# DINOBUS.net
KiCad netlist of a schematic drawn in Altium Designer
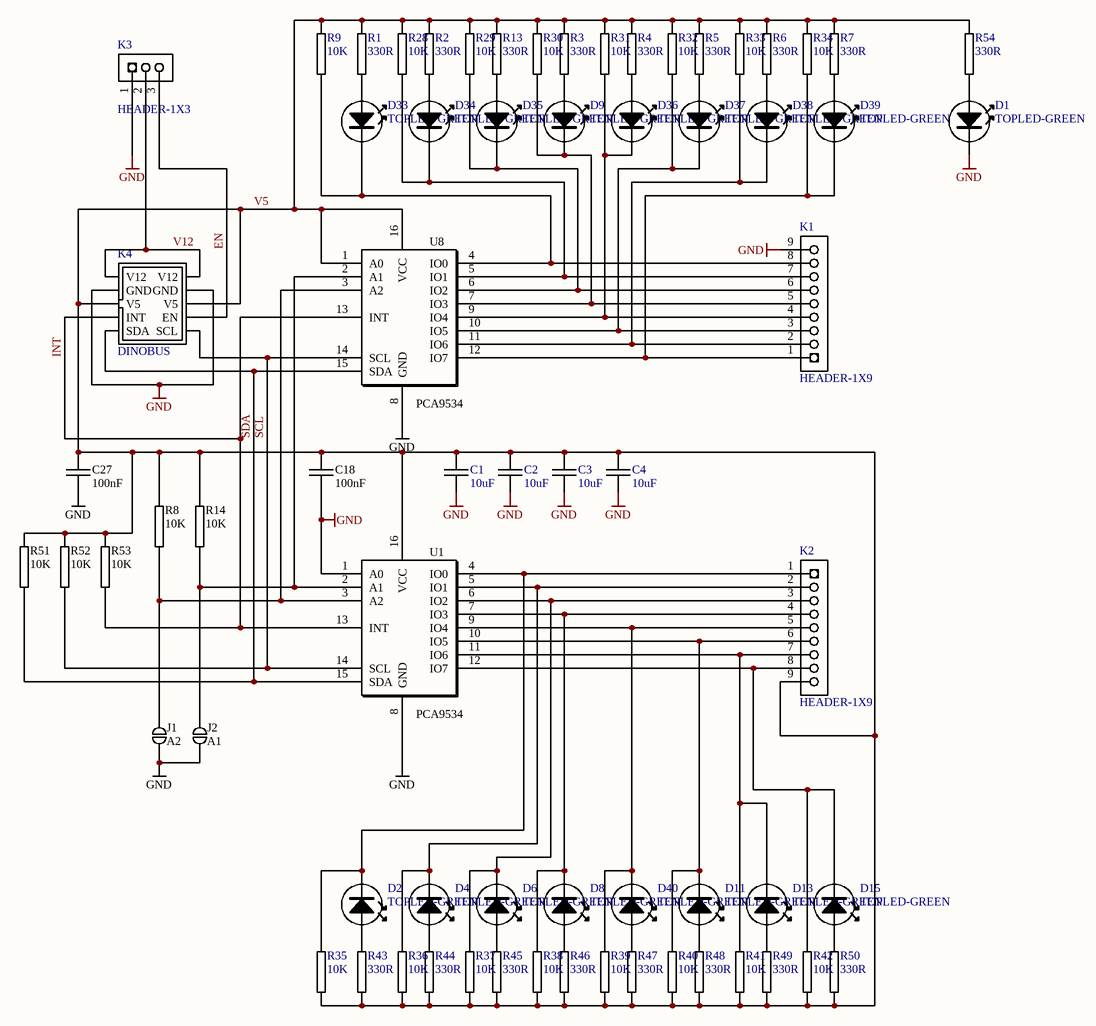
[diagram p0: DINOBUS .SchDoc]

(export (version "E")
  (design (tool "Eeschema 10.0.6"))
  (components
    (comp (ref "C1")
      (value "10uF")
      (footprint "0805C-GENERIC")
      (description "CAPACITOR 0805 CERAMIC")
      (fields
        (field (name "MANUFACTURER PART NUMBER") "C2012X5R1C106M")
        (field (name "MANUFACTURER") "TDK Corporation")
      )
      (libsource (lib "vh_Altium Library") (part "0805C-10UF-16V-X5R-TDK"))
    )
    (comp (ref "C2")
      (value "10uF")
      (footprint "0805C-GENERIC")
      (description "CAPACITOR 0805 CERAMIC")
      (fields
        (field (name "MANUFACTURER PART NUMBER") "C2012X5R1C106M")
        (field (name "MANUFACTURER") "TDK Corporation")
      )
      (libsource (lib "vh_Altium Library") (part "0805C-10UF-16V-X5R-TDK"))
    )
    (comp (ref "C3")
      (value "10uF")
      (footprint "0805C-GENERIC")
      (description "CAPACITOR 0805 CERAMIC")
      (fields
        (field (name "MANUFACTURER PART NUMBER") "C2012X5R1C106M")
        (field (name "MANUFACTURER") "TDK Corporation")
      )
      (libsource (lib "vh_Altium Library") (part "0805C-10UF-16V-X5R-TDK"))
    )
    (comp (ref "C4")
      (value "10uF")
      (footprint "0805C-GENERIC")
      (description "CAPACITOR 0805 CERAMIC")
      (fields
        (field (name "MANUFACTURER PART NUMBER") "C2012X5R1C106M")
        (field (name "MANUFACTURER") "TDK Corporation")
      )
      (libsource (lib "vh_Altium Library") (part "0805C-10UF-16V-X5R-TDK"))
    )
    (comp (ref "C18")
      (value "100nF")
      (footprint "0805C")
      (description "CAPACITOR NONPOLARISED")
      (libsource (lib "I2Csticks") (part "0805C-100NF"))
    )
    (comp (ref "C27")
      (value "100nF")
      (footprint "0805C")
      (description "CAPACITOR NONPOLARISED")
      (libsource (lib "I2Csticks") (part "0805C-100NF"))
    )
    (comp (ref "D1")
      (value "TOPLED-GREEN")
      (footprint "TOPLED-GREEN")
      (libsource (lib "vh_Altium Library") (part "TOPLED-GREEN"))
    )
    (comp (ref "D2")
      (value "TOPLED-GREEN")
      (footprint "TOPLED-GREEN")
      (libsource (lib "vh_Altium Library") (part "TOPLED-GREEN"))
    )
    (comp (ref "D4")
      (value "TOPLED-GREEN")
      (footprint "TOPLED-GREEN")
      (libsource (lib "vh_Altium Library") (part "TOPLED-GREEN"))
    )
    (comp (ref "D6")
      (value "TOPLED-GREEN")
      (footprint "TOPLED-GREEN")
      (libsource (lib "vh_Altium Library") (part "TOPLED-GREEN"))
    )
    (comp (ref "D8")
      (value "TOPLED-GREEN")
      (footprint "TOPLED-GREEN")
      (libsource (lib "vh_Altium Library") (part "TOPLED-GREEN"))
    )
    (comp (ref "D9")
      (value "TOPLED-GREEN")
      (footprint "TOPLED-GREEN")
      (libsource (lib "vh_Altium Library") (part "TOPLED-GREEN"))
    )
    (comp (ref "D11")
      (value "TOPLED-GREEN")
      (footprint "TOPLED-GREEN")
      (libsource (lib "vh_Altium Library") (part "TOPLED-GREEN"))
    )
    (comp (ref "D13")
      (value "TOPLED-GREEN")
      (footprint "TOPLED-GREEN")
      (libsource (lib "vh_Altium Library") (part "TOPLED-GREEN"))
    )
    (comp (ref "D15")
      (value "TOPLED-GREEN")
      (footprint "TOPLED-GREEN")
      (libsource (lib "vh_Altium Library") (part "TOPLED-GREEN"))
    )
    (comp (ref "D33")
      (value "TOPLED-GREEN")
      (footprint "TOPLED-GREEN")
      (libsource (lib "vh_Altium Library") (part "TOPLED-GREEN"))
    )
    (comp (ref "D34")
      (value "TOPLED-GREEN")
      (footprint "TOPLED-GREEN")
      (libsource (lib "vh_Altium Library") (part "TOPLED-GREEN"))
    )
    (comp (ref "D35")
      (value "TOPLED-GREEN")
      (footprint "TOPLED-GREEN")
      (libsource (lib "vh_Altium Library") (part "TOPLED-GREEN"))
    )
    (comp (ref "D36")
      (value "TOPLED-GREEN")
      (footprint "TOPLED-GREEN")
      (libsource (lib "vh_Altium Library") (part "TOPLED-GREEN"))
    )
    (comp (ref "D37")
      (value "TOPLED-GREEN")
      (footprint "TOPLED-GREEN")
      (libsource (lib "vh_Altium Library") (part "TOPLED-GREEN"))
    )
    (comp (ref "D38")
      (value "TOPLED-GREEN")
      (footprint "TOPLED-GREEN")
      (libsource (lib "vh_Altium Library") (part "TOPLED-GREEN"))
    )
    (comp (ref "D39")
      (value "TOPLED-GREEN")
      (footprint "TOPLED-GREEN")
      (libsource (lib "vh_Altium Library") (part "TOPLED-GREEN"))
    )
    (comp (ref "D40")
      (value "TOPLED-GREEN")
      (footprint "TOPLED-GREEN")
      (libsource (lib "vh_Altium Library") (part "TOPLED-GREEN"))
    )
    (comp (ref "J1") (value "A2") (footprint "BYPASS") (libsource (lib "*") (part "BYPASS")))
    (comp (ref "J2") (value "A1") (footprint "BYPASS") (libsource (lib "*") (part "BYPASS")))
    (comp (ref "K1")
      (value "HEADER-1X9")
      (footprint "HEADER-1X9")
      (libsource (lib "vh_Altium Library") (part "HEADER-1X9"))
    )
    (comp (ref "K2")
      (value "HEADER-1X9")
      (footprint "HEADER-1X9")
      (libsource (lib "vh_Altium Library") (part "HEADER-1X9"))
    )
    (comp (ref "K3")
      (value "HEADER-1X3")
      (footprint "HEADER-1X3")
      (libsource (lib "vh_Altium Library") (part "HEADER-1X3"))
    )
    (comp (ref "K4")
      (value "DINOBUS")
      (footprint "IDC10-B")
      (description "CONN HEADER LOW-PRO 10POS GOLD")
      (fields (field (name "MANUFACTURER") "Assmann Electronics Inc"))
      (libsource (lib "Schlib1") (part "DINOBUS"))
    )
    (comp (ref "R1")
      (value "330R")
      (footprint "0805R-330")
      (description "RESISTOR 0805 1/4 WATT THIN FILM")
      (libsource (lib "vh_Altium Library") (part "0805R-330"))
    )
    (comp (ref "R2")
      (value "330R")
      (footprint "0805R-330")
      (description "RESISTOR 0805 1/4 WATT THIN FILM")
      (libsource (lib "vh_Altium Library") (part "0805R-330"))
    )
    (comp (ref "R3")
      (value "330R")
      (footprint "0805R-330")
      (description "RESISTOR 0805 1/4 WATT THIN FILM")
      (libsource (lib "vh_Altium Library") (part "0805R-330"))
    )
    (comp (ref "R4")
      (value "330R")
      (footprint "0805R-330")
      (description "RESISTOR 0805 1/4 WATT THIN FILM")
      (libsource (lib "vh_Altium Library") (part "0805R-330"))
    )
    (comp (ref "R5")
      (value "330R")
      (footprint "0805R-330")
      (description "RESISTOR 0805 1/4 WATT THIN FILM")
      (libsource (lib "vh_Altium Library") (part "0805R-330"))
    )
    (comp (ref "R6")
      (value "330R")
      (footprint "0805R-330")
      (description "RESISTOR 0805 1/4 WATT THIN FILM")
      (libsource (lib "vh_Altium Library") (part "0805R-330"))
    )
    (comp (ref "R7")
      (value "330R")
      (footprint "0805R-330")
      (description "RESISTOR 0805 1/4 WATT THIN FILM")
      (libsource (lib "vh_Altium Library") (part "0805R-330"))
    )
    (comp (ref "R8")
      (value "10K")
      (footprint "0805R")
      (description "RESISTOR VALUE AS INDICATED")
      (libsource (lib "I2Csticks") (part "0805R-10K"))
    )
    (comp (ref "R9")
      (value "10K")
      (footprint "0805R-10K")
      (description "RESISTOR 0805 1/4 WATT THIN FILM")
      (libsource (lib "vh_Altium Library") (part "0805R-10K"))
    )
    (comp (ref "R13")
      (value "330R")
      (footprint "0805R-330")
      (description "RESISTOR 0805 1/4 WATT THIN FILM")
      (libsource (lib "vh_Altium Library") (part "0805R-330"))
    )
    (comp (ref "R14")
      (value "10K")
      (footprint "0805R")
      (description "RESISTOR VALUE AS INDICATED")
      (libsource (lib "I2Csticks") (part "0805R-10K"))
    )
    (comp (ref "R28")
      (value "10K")
      (footprint "0805R-10K")
      (description "RESISTOR 0805 1/4 WATT THIN FILM")
      (libsource (lib "vh_Altium Library") (part "0805R-10K"))
    )
    (comp (ref "R29")
      (value "10K")
      (footprint "0805R-10K")
      (description "RESISTOR 0805 1/4 WATT THIN FILM")
      (libsource (lib "vh_Altium Library") (part "0805R-10K"))
    )
    (comp (ref "R30")
      (value "10K")
      (footprint "0805R-10K")
      (description "RESISTOR 0805 1/4 WATT THIN FILM")
      (libsource (lib "vh_Altium Library") (part "0805R-10K"))
    )
    (comp (ref "R31")
      (value "10K")
      (footprint "0805R-10K")
      (description "RESISTOR 0805 1/4 WATT THIN FILM")
      (libsource (lib "vh_Altium Library") (part "0805R-10K"))
    )
    (comp (ref "R32")
      (value "10K")
      (footprint "0805R-10K")
      (description "RESISTOR 0805 1/4 WATT THIN FILM")
      (libsource (lib "vh_Altium Library") (part "0805R-10K"))
    )
    (comp (ref "R33")
      (value "10K")
      (footprint "0805R-10K")
      (description "RESISTOR 0805 1/4 WATT THIN FILM")
      (libsource (lib "vh_Altium Library") (part "0805R-10K"))
    )
    (comp (ref "R34")
      (value "10K")
      (footprint "0805R-10K")
      (description "RESISTOR 0805 1/4 WATT THIN FILM")
      (libsource (lib "vh_Altium Library") (part "0805R-10K"))
    )
    (comp (ref "R35")
      (value "10K")
      (footprint "0805R-10K")
      (description "RESISTOR 0805 1/4 WATT THIN FILM")
      (libsource (lib "vh_Altium Library") (part "0805R-10K"))
    )
    (comp (ref "R36")
      (value "10K")
      (footprint "0805R-10K")
      (description "RESISTOR 0805 1/4 WATT THIN FILM")
      (libsource (lib "vh_Altium Library") (part "0805R-10K"))
    )
    (comp (ref "R37")
      (value "10K")
      (footprint "0805R-10K")
      (description "RESISTOR 0805 1/4 WATT THIN FILM")
      (libsource (lib "vh_Altium Library") (part "0805R-10K"))
    )
    (comp (ref "R38")
      (value "10K")
      (footprint "0805R-10K")
      (description "RESISTOR 0805 1/4 WATT THIN FILM")
      (libsource (lib "vh_Altium Library") (part "0805R-10K"))
    )
    (comp (ref "R39")
      (value "10K")
      (footprint "0805R-10K")
      (description "RESISTOR 0805 1/4 WATT THIN FILM")
      (libsource (lib "vh_Altium Library") (part "0805R-10K"))
    )
    (comp (ref "R40")
      (value "10K")
      (footprint "0805R-10K")
      (description "RESISTOR 0805 1/4 WATT THIN FILM")
      (libsource (lib "vh_Altium Library") (part "0805R-10K"))
    )
    (comp (ref "R41")
      (value "10K")
      (footprint "0805R-10K")
      (description "RESISTOR 0805 1/4 WATT THIN FILM")
      (libsource (lib "vh_Altium Library") (part "0805R-10K"))
    )
    (comp (ref "R42")
      (value "10K")
      (footprint "0805R-10K")
      (description "RESISTOR 0805 1/4 WATT THIN FILM")
      (libsource (lib "vh_Altium Library") (part "0805R-10K"))
    )
    (comp (ref "R43")
      (value "330R")
      (footprint "0805R-330")
      (description "RESISTOR 0805 1/4 WATT THIN FILM")
      (libsource (lib "vh_Altium Library") (part "0805R-330"))
    )
    (comp (ref "R44")
      (value "330R")
      (footprint "0805R-330")
      (description "RESISTOR 0805 1/4 WATT THIN FILM")
      (libsource (lib "vh_Altium Library") (part "0805R-330"))
    )
    (comp (ref "R45")
      (value "330R")
      (footprint "0805R-330")
      (description "RESISTOR 0805 1/4 WATT THIN FILM")
      (libsource (lib "vh_Altium Library") (part "0805R-330"))
    )
    (comp (ref "R46")
      (value "330R")
      (footprint "0805R-330")
      (description "RESISTOR 0805 1/4 WATT THIN FILM")
      (libsource (lib "vh_Altium Library") (part "0805R-330"))
    )
    (comp (ref "R47")
      (value "330R")
      (footprint "0805R-330")
      (description "RESISTOR 0805 1/4 WATT THIN FILM")
      (libsource (lib "vh_Altium Library") (part "0805R-330"))
    )
    (comp (ref "R48")
      (value "330R")
      (footprint "0805R-330")
      (description "RESISTOR 0805 1/4 WATT THIN FILM")
      (libsource (lib "vh_Altium Library") (part "0805R-330"))
    )
    (comp (ref "R49")
      (value "330R")
      (footprint "0805R-330")
      (description "RESISTOR 0805 1/4 WATT THIN FILM")
      (libsource (lib "vh_Altium Library") (part "0805R-330"))
    )
    (comp (ref "R50")
      (value "330R")
      (footprint "0805R-330")
      (description "RESISTOR 0805 1/4 WATT THIN FILM")
      (libsource (lib "vh_Altium Library") (part "0805R-330"))
    )
    (comp (ref "R51")
      (value "10K")
      (footprint "0805R")
      (description "RESISTOR VALUE AS INDICATED")
      (libsource (lib "I2Csticks") (part "0805R-10K"))
    )
    (comp (ref "R52")
      (value "10K")
      (footprint "0805R")
      (description "RESISTOR VALUE AS INDICATED")
      (libsource (lib "I2Csticks") (part "0805R-10K"))
    )
    (comp (ref "R53")
      (value "10K")
      (footprint "0805R")
      (description "RESISTOR VALUE AS INDICATED")
      (libsource (lib "I2Csticks") (part "0805R-10K"))
    )
    (comp (ref "R54")
      (value "330R")
      (footprint "0805R-330")
      (description "RESISTOR 0805 1/4 WATT THIN FILM")
      (libsource (lib "vh_Altium Library") (part "0805R-330"))
    )
    (comp (ref "U1")
      (value "PCA9534")
      (footprint "SO16W")
      (description "OCTAL PUSH PULL DRIVER I2C")
      (libsource (lib "*") (part "PCA9534"))
    )
    (comp (ref "U8")
      (value "PCA9534")
      (footprint "SO16W")
      (description "OCTAL PUSH PULL DRIVER I2C")
      (libsource (lib "*") (part "PCA9534"))
    )
  )
  (nets
    (net (code "1") (name "/EN") (class "Default")
      (node (ref "K3") (pin "3") (pintype "passive"))
      (node (ref "K4") (pin "8") (pinfunction "EN_8") (pintype "passive"))
    )
    (net (code "2") (name "/INT") (class "Default")
      (node (ref "K4") (pin "7") (pinfunction "INT_7") (pintype "passive"))
      (node (ref "R53") (pin "1") (pintype "passive"))
      (node (ref "U1") (pin "13") (pinfunction "INT_13") (pintype "passive"))
      (node (ref "U8") (pin "13") (pinfunction "INT_13") (pintype "passive"))
    )
    (net (code "3") (name "/SCL") (class "Default")
      (node (ref "K4") (pin "10") (pinfunction "SCL_10") (pintype "passive"))
      (node (ref "R52") (pin "1") (pintype "passive"))
      (node (ref "U1") (pin "14") (pinfunction "SCL_14") (pintype "passive"))
      (node (ref "U8") (pin "14") (pinfunction "SCL_14") (pintype "passive"))
    )
    (net (code "4") (name "/SDA") (class "Default")
      (node (ref "K4") (pin "9") (pinfunction "SDA_9") (pintype "passive"))
      (node (ref "R51") (pin "1") (pintype "passive"))
      (node (ref "U1") (pin "15") (pinfunction "SDA_15") (pintype "passive"))
      (node (ref "U8") (pin "15") (pinfunction "SDA_15") (pintype "passive"))
    )
    (net (code "5") (name "/V5") (class "Default")
      (node (ref "C1") (pin "1") (pintype "passive"))
      (node (ref "C18") (pin "1") (pintype "passive"))
      (node (ref "C2") (pin "1") (pintype "passive"))
      (node (ref "C27") (pin "1") (pintype "passive"))
      (node (ref "C3") (pin "1") (pintype "passive"))
      (node (ref "C4") (pin "1") (pintype "passive"))
      (node (ref "K2") (pin "9") (pintype "passive"))
      (node (ref "K4") (pin "5") (pinfunction "V5_5") (pintype "passive"))
      (node (ref "K4") (pin "6") (pinfunction "V5_6") (pintype "passive"))
      (node (ref "R1") (pin "2") (pintype "passive"))
      (node (ref "R13") (pin "2") (pintype "passive"))
      (node (ref "R14") (pin "2") (pintype "passive"))
      (node (ref "R2") (pin "2") (pintype "passive"))
      (node (ref "R28") (pin "2") (pintype "passive"))
      (node (ref "R29") (pin "2") (pintype "passive"))
      (node (ref "R3") (pin "2") (pintype "passive"))
      (node (ref "R30") (pin "2") (pintype "passive"))
      (node (ref "R31") (pin "2") (pintype "passive"))
      (node (ref "R32") (pin "2") (pintype "passive"))
      (node (ref "R33") (pin "2") (pintype "passive"))
      (node (ref "R34") (pin "2") (pintype "passive"))
      (node (ref "R35") (pin "2") (pintype "passive"))
      (node (ref "R36") (pin "2") (pintype "passive"))
      (node (ref "R37") (pin "2") (pintype "passive"))
      (node (ref "R38") (pin "2") (pintype "passive"))
      (node (ref "R39") (pin "2") (pintype "passive"))
      (node (ref "R4") (pin "2") (pintype "passive"))
      (node (ref "R40") (pin "2") (pintype "passive"))
      (node (ref "R41") (pin "2") (pintype "passive"))
      (node (ref "R42") (pin "2") (pintype "passive"))
      (node (ref "R43") (pin "2") (pintype "passive"))
      (node (ref "R44") (pin "2") (pintype "passive"))
      (node (ref "R45") (pin "2") (pintype "passive"))
      (node (ref "R46") (pin "2") (pintype "passive"))
      (node (ref "R47") (pin "2") (pintype "passive"))
      (node (ref "R48") (pin "2") (pintype "passive"))
      (node (ref "R49") (pin "2") (pintype "passive"))
      (node (ref "R5") (pin "2") (pintype "passive"))
      (node (ref "R50") (pin "2") (pintype "passive"))
      (node (ref "R51") (pin "2") (pintype "passive"))
      (node (ref "R52") (pin "2") (pintype "passive"))
      (node (ref "R53") (pin "2") (pintype "passive"))
      (node (ref "R54") (pin "2") (pintype "passive"))
      (node (ref "R6") (pin "2") (pintype "passive"))
      (node (ref "R7") (pin "2") (pintype "passive"))
      (node (ref "R8") (pin "2") (pintype "passive"))
      (node (ref "R9") (pin "2") (pintype "passive"))
      (node (ref "U1") (pin "16") (pinfunction "VCC_16") (pintype "passive"))
      (node (ref "U8") (pin "1") (pinfunction "A0_1") (pintype "passive"))
      (node (ref "U8") (pin "16") (pinfunction "VCC_16") (pintype "passive"))
    )
    (net (code "6") (name "/V12") (class "Default")
      (node (ref "K3") (pin "2") (pintype "passive"))
      (node (ref "K4") (pin "1") (pinfunction "V12_1") (pintype "passive"))
      (node (ref "K4") (pin "2") (pinfunction "V12_2") (pintype "passive"))
    )
    (net (code "7") (name "GND") (class "Default")
      (node (ref "C1") (pin "2") (pintype "passive"))
      (node (ref "C18") (pin "2") (pintype "passive"))
      (node (ref "C2") (pin "2") (pintype "passive"))
      (node (ref "C27") (pin "2") (pintype "passive"))
      (node (ref "C3") (pin "2") (pintype "passive"))
      (node (ref "C4") (pin "2") (pintype "passive"))
      (node (ref "D1") (pin "K") (pintype "passive"))
      (node (ref "J1") (pin "2") (pinfunction "2_2") (pintype "passive"))
      (node (ref "J2") (pin "2") (pinfunction "2_2") (pintype "passive"))
      (node (ref "K1") (pin "9") (pintype "passive"))
      (node (ref "K3") (pin "1") (pintype "passive"))
      (node (ref "K4") (pin "3") (pinfunction "GND_3") (pintype "passive"))
      (node (ref "K4") (pin "4") (pinfunction "GND_4") (pintype "passive"))
      (node (ref "U1") (pin "1") (pinfunction "A0_1") (pintype "passive"))
      (node (ref "U1") (pin "8") (pinfunction "GND_8") (pintype "passive"))
      (node (ref "U8") (pin "8") (pinfunction "GND_8") (pintype "passive"))
    )
    (net (code "8") (name "Net-(D1-PadA)") (class "Default")
      (node (ref "D1") (pin "A") (pintype "passive"))
      (node (ref "R54") (pin "1") (pintype "passive"))
    )
    (net (code "9") (name "Net-(D2-PadA)") (class "Default")
      (node (ref "D2") (pin "A") (pintype "passive"))
      (node (ref "R43") (pin "1") (pintype "passive"))
    )
    (net (code "10") (name "Net-(D4-PadA)") (class "Default")
      (node (ref "D4") (pin "A") (pintype "passive"))
      (node (ref "R44") (pin "1") (pintype "passive"))
    )
    (net (code "11") (name "Net-(D6-PadA)") (class "Default")
      (node (ref "D6") (pin "A") (pintype "passive"))
      (node (ref "R45") (pin "1") (pintype "passive"))
    )
    (net (code "12") (name "Net-(D8-PadA)") (class "Default")
      (node (ref "D8") (pin "A") (pintype "passive"))
      (node (ref "R46") (pin "1") (pintype "passive"))
    )
    (net (code "13") (name "Net-(D9-PadA)") (class "Default")
      (node (ref "D9") (pin "A") (pintype "passive"))
      (node (ref "R3") (pin "1") (pintype "passive"))
    )
    (net (code "14") (name "Net-(D11-PadA)") (class "Default")
      (node (ref "D11") (pin "A") (pintype "passive"))
      (node (ref "R48") (pin "1") (pintype "passive"))
    )
    (net (code "15") (name "Net-(D13-PadA)") (class "Default")
      (node (ref "D13") (pin "A") (pintype "passive"))
      (node (ref "R49") (pin "1") (pintype "passive"))
    )
    (net (code "16") (name "Net-(D15-PadA)") (class "Default")
      (node (ref "D15") (pin "A") (pintype "passive"))
      (node (ref "R50") (pin "1") (pintype "passive"))
    )
    (net (code "17") (name "Net-(D33-PadA)") (class "Default")
      (node (ref "D33") (pin "A") (pintype "passive"))
      (node (ref "R1") (pin "1") (pintype "passive"))
    )
    (net (code "18") (name "Net-(D34-PadA)") (class "Default")
      (node (ref "D34") (pin "A") (pintype "passive"))
      (node (ref "R2") (pin "1") (pintype "passive"))
    )
    (net (code "19") (name "Net-(D35-PadA)") (class "Default")
      (node (ref "D35") (pin "A") (pintype "passive"))
      (node (ref "R13") (pin "1") (pintype "passive"))
    )
    (net (code "20") (name "Net-(D36-PadA)") (class "Default")
      (node (ref "D36") (pin "A") (pintype "passive"))
      (node (ref "R4") (pin "1") (pintype "passive"))
    )
    (net (code "21") (name "Net-(D37-PadA)") (class "Default")
      (node (ref "D37") (pin "A") (pintype "passive"))
      (node (ref "R5") (pin "1") (pintype "passive"))
    )
    (net (code "22") (name "Net-(D38-PadA)") (class "Default")
      (node (ref "D38") (pin "A") (pintype "passive"))
      (node (ref "R6") (pin "1") (pintype "passive"))
    )
    (net (code "23") (name "Net-(D39-PadA)") (class "Default")
      (node (ref "D39") (pin "A") (pintype "passive"))
      (node (ref "R7") (pin "1") (pintype "passive"))
    )
    (net (code "24") (name "Net-(D40-PadA)") (class "Default")
      (node (ref "D40") (pin "A") (pintype "passive"))
      (node (ref "R47") (pin "1") (pintype "passive"))
    )
    (net (code "25") (name "Net-(U1-A1)") (class "Default")
      (node (ref "J2") (pin "1") (pinfunction "1_1") (pintype "passive"))
      (node (ref "R14") (pin "1") (pintype "passive"))
      (node (ref "U1") (pin "2") (pinfunction "A1_2") (pintype "passive"))
      (node (ref "U8") (pin "2") (pinfunction "A1_2") (pintype "passive"))
    )
    (net (code "26") (name "Net-(U1-A2)") (class "Default")
      (node (ref "J1") (pin "1") (pinfunction "1_1") (pintype "passive"))
      (node (ref "R8") (pin "1") (pintype "passive"))
      (node (ref "U1") (pin "3") (pinfunction "A2_3") (pintype "passive"))
      (node (ref "U8") (pin "3") (pinfunction "A2_3") (pintype "passive"))
    )
    (net (code "27") (name "Net-(U1-IO0)") (class "Default")
      (node (ref "D2") (pin "K") (pintype "passive"))
      (node (ref "K2") (pin "1") (pintype "passive"))
      (node (ref "R35") (pin "1") (pintype "passive"))
      (node (ref "U1") (pin "4") (pinfunction "IO0_4") (pintype "passive"))
    )
    (net (code "28") (name "Net-(U1-IO1)") (class "Default")
      (node (ref "D4") (pin "K") (pintype "passive"))
      (node (ref "K2") (pin "2") (pintype "passive"))
      (node (ref "R36") (pin "1") (pintype "passive"))
      (node (ref "U1") (pin "5") (pinfunction "IO1_5") (pintype "passive"))
    )
    (net (code "29") (name "Net-(U1-IO2)") (class "Default")
      (node (ref "D6") (pin "K") (pintype "passive"))
      (node (ref "K2") (pin "3") (pintype "passive"))
      (node (ref "R37") (pin "1") (pintype "passive"))
      (node (ref "U1") (pin "6") (pinfunction "IO2_6") (pintype "passive"))
    )
    (net (code "30") (name "Net-(U1-IO3)") (class "Default")
      (node (ref "D8") (pin "K") (pintype "passive"))
      (node (ref "K2") (pin "4") (pintype "passive"))
      (node (ref "R38") (pin "1") (pintype "passive"))
      (node (ref "U1") (pin "7") (pinfunction "IO3_7") (pintype "passive"))
    )
    (net (code "31") (name "Net-(U1-IO4)") (class "Default")
      (node (ref "D40") (pin "K") (pintype "passive"))
      (node (ref "K2") (pin "5") (pintype "passive"))
      (node (ref "R39") (pin "1") (pintype "passive"))
      (node (ref "U1") (pin "9") (pinfunction "IO4_9") (pintype "passive"))
    )
    (net (code "32") (name "Net-(U1-IO5)") (class "Default")
      (node (ref "D11") (pin "K") (pintype "passive"))
      (node (ref "K2") (pin "6") (pintype "passive"))
      (node (ref "R40") (pin "1") (pintype "passive"))
      (node (ref "U1") (pin "10") (pinfunction "IO5_10") (pintype "passive"))
    )
    (net (code "33") (name "Net-(U1-IO6)") (class "Default")
      (node (ref "D13") (pin "K") (pintype "passive"))
      (node (ref "K2") (pin "7") (pintype "passive"))
      (node (ref "R41") (pin "1") (pintype "passive"))
      (node (ref "U1") (pin "11") (pinfunction "IO6_11") (pintype "passive"))
    )
    (net (code "34") (name "Net-(U1-IO7)") (class "Default")
      (node (ref "D15") (pin "K") (pintype "passive"))
      (node (ref "K2") (pin "8") (pintype "passive"))
      (node (ref "R42") (pin "1") (pintype "passive"))
      (node (ref "U1") (pin "12") (pinfunction "IO7_12") (pintype "passive"))
    )
    (net (code "35") (name "Net-(U8-IO0)") (class "Default")
      (node (ref "D33") (pin "K") (pintype "passive"))
      (node (ref "K1") (pin "8") (pintype "passive"))
      (node (ref "R9") (pin "1") (pintype "passive"))
      (node (ref "U8") (pin "4") (pinfunction "IO0_4") (pintype "passive"))
    )
    (net (code "36") (name "Net-(U8-IO1)") (class "Default")
      (node (ref "D34") (pin "K") (pintype "passive"))
      (node (ref "K1") (pin "7") (pintype "passive"))
      (node (ref "R28") (pin "1") (pintype "passive"))
      (node (ref "U8") (pin "5") (pinfunction "IO1_5") (pintype "passive"))
    )
    (net (code "37") (name "Net-(U8-IO2)") (class "Default")
      (node (ref "D35") (pin "K") (pintype "passive"))
      (node (ref "K1") (pin "6") (pintype "passive"))
      (node (ref "R29") (pin "1") (pintype "passive"))
      (node (ref "U8") (pin "6") (pinfunction "IO2_6") (pintype "passive"))
    )
    (net (code "38") (name "Net-(U8-IO3)") (class "Default")
      (node (ref "D9") (pin "K") (pintype "passive"))
      (node (ref "K1") (pin "5") (pintype "passive"))
      (node (ref "R30") (pin "1") (pintype "passive"))
      (node (ref "U8") (pin "7") (pinfunction "IO3_7") (pintype "passive"))
    )
    (net (code "39") (name "Net-(U8-IO4)") (class "Default")
      (node (ref "D36") (pin "K") (pintype "passive"))
      (node (ref "K1") (pin "4") (pintype "passive"))
      (node (ref "R31") (pin "1") (pintype "passive"))
      (node (ref "U8") (pin "9") (pinfunction "IO4_9") (pintype "passive"))
    )
    (net (code "40") (name "Net-(U8-IO5)") (class "Default")
      (node (ref "D37") (pin "K") (pintype "passive"))
      (node (ref "K1") (pin "3") (pintype "passive"))
      (node (ref "R32") (pin "1") (pintype "passive"))
      (node (ref "U8") (pin "10") (pinfunction "IO5_10") (pintype "passive"))
    )
    (net (code "41") (name "Net-(U8-IO6)") (class "Default")
      (node (ref "D38") (pin "K") (pintype "passive"))
      (node (ref "K1") (pin "2") (pintype "passive"))
      (node (ref "R33") (pin "1") (pintype "passive"))
      (node (ref "U8") (pin "11") (pinfunction "IO6_11") (pintype "passive"))
    )
    (net (code "42") (name "Net-(U8-IO7)") (class "Default")
      (node (ref "D39") (pin "K") (pintype "passive"))
      (node (ref "K1") (pin "1") (pintype "passive"))
      (node (ref "R34") (pin "1") (pintype "passive"))
      (node (ref "U8") (pin "12") (pinfunction "IO7_12") (pintype "passive"))
    )
  )
)
